# BleShield.net
KiCad netlist of a schematic drawn in EAGLE
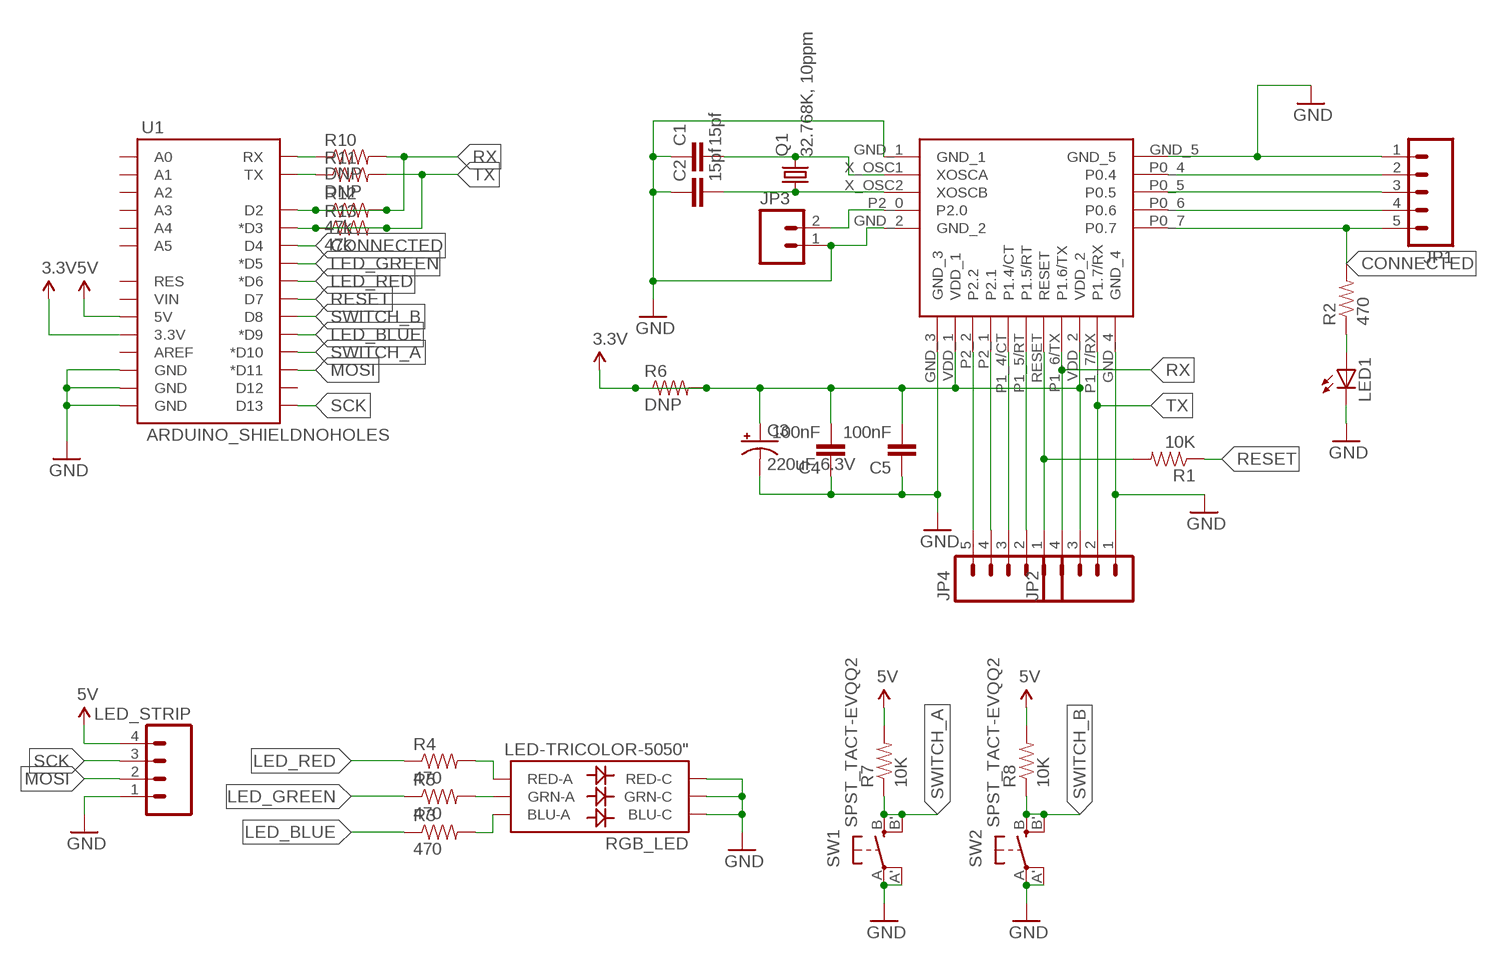
[diagram p0: schematic, sheet 1]

(export (version "E")
  (design (tool "Eeschema 10.0.6"))
  (components
    (comp (ref "C1")
      (value "15pf")
      (footprint "eagle-import:0805")
      (libsource (lib "eagle-import") (part "CAP0805"))
    )
    (comp (ref "C2")
      (value "15pf")
      (footprint "eagle-import:0805")
      (libsource (lib "eagle-import") (part "CAP0805"))
    )
    (comp (ref "C3")
      (value "220uF 6.3V")
      (footprint "eagle-import:C_6032-28R")
      (libsource (lib "eagle-import") (part "CPOL-USC/6032-28R"))
    )
    (comp (ref "C4")
      (value "100nF")
      (footprint "eagle-import:0805")
      (libsource (lib "eagle-import") (part "CAP0805"))
    )
    (comp (ref "C5")
      (value "100nF")
      (footprint "eagle-import:0805")
      (libsource (lib "eagle-import") (part "CAP0805"))
    )
    (comp (ref "JP1")
      (value "M051.27MM")
      (footprint "eagle-import:1X05-1.27MM")
      (libsource (lib "eagle-import") (part "M051.27MM"))
    )
    (comp (ref "JP2")
      (value "M041.27MM")
      (footprint "eagle-import:1X04-1.27MM")
      (libsource (lib "eagle-import") (part "M041.27MM"))
    )
    (comp (ref "JP3")
      (value "M02")
      (footprint "eagle-import:1X02-1.27MM")
      (libsource (lib "eagle-import") (part "M02"))
    )
    (comp (ref "JP4")
      (value "M051.27MM")
      (footprint "eagle-import:1X05-1.27MM")
      (libsource (lib "eagle-import") (part "M051.27MM"))
    )
    (comp (ref "LED1")
      (value "LEDCHIPLED_0805")
      (footprint "eagle-import:CHIPLED_0805")
      (libsource (lib "eagle-import") (part "LEDCHIPLED_0805"))
    )
    (comp (ref "LED_STRIP")
      (value "M04PTH")
      (footprint "eagle-import:1X04")
      (libsource (lib "eagle-import") (part "M04PTH"))
    )
    (comp (ref "Q1")
      (value "32.768K, 10ppm")
      (footprint "eagle-import:CRYSTAL_3215")
      (libsource (lib "eagle-import") (part "CRYSTAL3215"))
    )
    (comp (ref "R1")
      (value "10K")
      (footprint "eagle-import:0805")
      (libsource (lib "eagle-import") (part "RESISTOR0805-RES"))
    )
    (comp (ref "R2")
      (value "470")
      (footprint "eagle-import:0805")
      (libsource (lib "eagle-import") (part "RESISTOR0805-RES"))
    )
    (comp (ref "R3")
      (value "470")
      (footprint "eagle-import:0805")
      (libsource (lib "eagle-import") (part "RESISTOR0805-RES"))
    )
    (comp (ref "R4")
      (value "470")
      (footprint "eagle-import:0805")
      (libsource (lib "eagle-import") (part "RESISTOR0805-RES"))
    )
    (comp (ref "R5")
      (value "470")
      (footprint "eagle-import:0805")
      (libsource (lib "eagle-import") (part "RESISTOR0805-RES"))
    )
    (comp (ref "R6")
      (value "DNP")
      (footprint "eagle-import:0805")
      (libsource (lib "eagle-import") (part "RESISTOR0805-RES"))
    )
    (comp (ref "R7")
      (value "10K")
      (footprint "eagle-import:0805")
      (libsource (lib "eagle-import") (part "RESISTOR0805-RES"))
    )
    (comp (ref "R8")
      (value "10K")
      (footprint "eagle-import:0805")
      (libsource (lib "eagle-import") (part "RESISTOR0805-RES"))
    )
    (comp (ref "R10")
      (value "DNP")
      (footprint "eagle-import:0805")
      (libsource (lib "eagle-import") (part "RESISTOR0805-RES"))
    )
    (comp (ref "R11")
      (value "DNP")
      (footprint "eagle-import:0805")
      (libsource (lib "eagle-import") (part "RESISTOR0805-RES"))
    )
    (comp (ref "R12")
      (value "47k")
      (footprint "eagle-import:0805")
      (libsource (lib "eagle-import") (part "RESISTOR0805-RES"))
    )
    (comp (ref "R13")
      (value "47k")
      (footprint "eagle-import:0805")
      (libsource (lib "eagle-import") (part "RESISTOR0805-RES"))
    )
    (comp (ref "RGB_LED")
      (value "LED-TRICOLOR-5050\"")
      (footprint "eagle-import:LED-TRICOLOR-5050-FIXED")
      (libsource (lib "eagle-import") (part "LED-TRICOLOR-5050{dblquote}"))
    )
    (comp (ref "SW1")
      (value "SPST_TACT-EVQQ2")
      (footprint "eagle-import:EVQ-Q2")
      (libsource (lib "eagle-import") (part "SPST_TACT-EVQQ2"))
    )
    (comp (ref "SW2")
      (value "SPST_TACT-EVQQ2")
      (footprint "eagle-import:EVQ-Q2")
      (libsource (lib "eagle-import") (part "SPST_TACT-EVQQ2"))
    )
    (comp (ref "U$1")
      (value "BG213L")
      (footprint "eagle-import:BG312L")
      (libsource (lib "eagle-import") (part "BG213L"))
    )
    (comp (ref "U1")
      (value "ARDUINO_SHIELDNOHOLES")
      (footprint "eagle-import:DUEMILANOVE_SHIELD_NOHOLES")
      (libsource (lib "eagle-import") (part "ARDUINO_SHIELDNOHOLES"))
    )
  )
  (nets
    (net (code "1") (name "3.3V") (class "Default")
      (node (ref "C3") (pin "+") (pinfunction "+_+") (pintype "passive"))
      (node (ref "C4") (pin "2") (pinfunction "2_2") (pintype "passive"))
      (node (ref "C5") (pin "2") (pinfunction "2_2") (pintype "passive"))
      (node (ref "JP2") (pin "3") (pinfunction "3_3") (pintype "passive"))
      (node (ref "R6") (pin "1") (pinfunction "1_1") (pintype "passive"))
      (node (ref "R6") (pin "2") (pinfunction "2_2") (pintype "passive"))
      (node (ref "U$1") (pin "VDD_1") (pinfunction "VDD_1_VDD_1") (pintype "bidirectional"))
      (node (ref "U$1") (pin "VDD_2") (pinfunction "VDD_2_VDD_2") (pintype "bidirectional"))
      (node (ref "U1") (pin "3.3V") (pinfunction "3.3V_3.3V") (pintype "bidirectional"))
    )
    (net (code "2") (name "5V") (class "Default")
      (node (ref "LED_STRIP") (pin "4") (pinfunction "4_4") (pintype "passive"))
      (node (ref "R7") (pin "2") (pinfunction "2_2") (pintype "passive"))
      (node (ref "R8") (pin "2") (pinfunction "2_2") (pintype "passive"))
      (node (ref "U1") (pin "5V") (pinfunction "5V_5V") (pintype "bidirectional"))
    )
    (net (code "3") (name "CONNECTED") (class "Default")
      (node (ref "JP1") (pin "5") (pinfunction "5_5") (pintype "passive"))
      (node (ref "R2") (pin "2") (pinfunction "2_2") (pintype "passive"))
      (node (ref "U$1") (pin "P0_7") (pinfunction "P0.7_P0_7") (pintype "bidirectional"))
      (node (ref "U1") (pin "D4") (pinfunction "D4_D4") (pintype "bidirectional"))
    )
    (net (code "4") (name "GND") (class "Default")
      (node (ref "C1") (pin "1") (pinfunction "1_1") (pintype "passive"))
      (node (ref "C2") (pin "1") (pinfunction "1_1") (pintype "passive"))
      (node (ref "C3") (pin "-") (pinfunction "-_-") (pintype "passive"))
      (node (ref "C4") (pin "1") (pinfunction "1_1") (pintype "passive"))
      (node (ref "C5") (pin "1") (pinfunction "1_1") (pintype "passive"))
      (node (ref "JP1") (pin "1") (pinfunction "1_1") (pintype "passive"))
      (node (ref "JP2") (pin "1") (pinfunction "1_1") (pintype "passive"))
      (node (ref "JP3") (pin "1") (pinfunction "1_1") (pintype "passive"))
      (node (ref "LED1") (pin "C") (pinfunction "C_C") (pintype "passive"))
      (node (ref "LED_STRIP") (pin "1") (pinfunction "1_1") (pintype "passive"))
      (node (ref "RGB_LED") (pin "1") (pinfunction "BLU-C_1") (pintype "bidirectional"))
      (node (ref "RGB_LED") (pin "2") (pinfunction "RED-C_2") (pintype "bidirectional"))
      (node (ref "RGB_LED") (pin "3") (pinfunction "GRN-C_3") (pintype "bidirectional"))
      (node (ref "SW1") (pin "A") (pinfunction "P_A") (pintype "passive"))
      (node (ref "SW1") (pin "A'") (pinfunction "P1_A'") (pintype "passive"))
      (node (ref "SW2") (pin "A") (pinfunction "P_A") (pintype "passive"))
      (node (ref "SW2") (pin "A'") (pinfunction "P1_A'") (pintype "passive"))
      (node (ref "U$1") (pin "GND_1") (pinfunction "GND_1_GND_1") (pintype "bidirectional"))
      (node (ref "U$1") (pin "GND_2") (pinfunction "GND_2_GND_2") (pintype "bidirectional"))
      (node (ref "U$1") (pin "GND_3") (pinfunction "GND_3_GND_3") (pintype "bidirectional"))
      (node (ref "U$1") (pin "GND_4") (pinfunction "GND_4_GND_4") (pintype "bidirectional"))
      (node (ref "U$1") (pin "GND_5") (pinfunction "GND_5_GND_5") (pintype "bidirectional"))
      (node (ref "U1") (pin "GND@0") (pinfunction "GND_GND@0") (pintype "bidirectional"))
      (node (ref "U1") (pin "GND@1") (pinfunction "GND_GND@1") (pintype "bidirectional"))
      (node (ref "U1") (pin "GND@2") (pinfunction "GND_GND@2") (pintype "bidirectional"))
    )
    (net (code "5") (name "LED_BLUE") (class "Default")
      (node (ref "R3") (pin "1") (pinfunction "1_1") (pintype "passive"))
      (node (ref "U1") (pin "D9") (pinfunction "*D9_D9") (pintype "bidirectional"))
    )
    (net (code "6") (name "LED_GREEN") (class "Default")
      (node (ref "R5") (pin "1") (pinfunction "1_1") (pintype "passive"))
      (node (ref "U1") (pin "D5") (pinfunction "*D5_D5") (pintype "bidirectional"))
    )
    (net (code "7") (name "LED_RED") (class "Default")
      (node (ref "R4") (pin "1") (pinfunction "1_1") (pintype "passive"))
      (node (ref "U1") (pin "D6") (pinfunction "*D6_D6") (pintype "bidirectional"))
    )
    (net (code "8") (name "MOSI") (class "Default")
      (node (ref "LED_STRIP") (pin "2") (pinfunction "2_2") (pintype "passive"))
      (node (ref "U1") (pin "D11") (pinfunction "*D11_D11") (pintype "bidirectional"))
    )
    (net (code "9") (name "Net-(JP4-Pad1)") (class "Default")
      (node (ref "JP4") (pin "1") (pinfunction "1_1") (pintype "passive"))
      (node (ref "R1") (pin "2") (pinfunction "2_2") (pintype "passive"))
      (node (ref "U$1") (pin "RESET") (pinfunction "RESET_RESET") (pintype "bidirectional"))
    )
    (net (code "10") (name "Net-(LED1-PadA)") (class "Default")
      (node (ref "LED1") (pin "A") (pinfunction "A_A") (pintype "passive"))
      (node (ref "R2") (pin "1") (pinfunction "1_1") (pintype "passive"))
    )
    (net (code "11") (name "Net-(Q1-1)") (class "Default")
      (node (ref "C2") (pin "2") (pinfunction "2_2") (pintype "passive"))
      (node (ref "Q1") (pin "P$1") (pinfunction "1_P$1") (pintype "passive"))
      (node (ref "U$1") (pin "X_OSC2") (pinfunction "XOSCB_X_OSC2") (pintype "bidirectional"))
    )
    (net (code "12") (name "Net-(Q1-2)") (class "Default")
      (node (ref "C1") (pin "2") (pinfunction "2_2") (pintype "passive"))
      (node (ref "Q1") (pin "P$2") (pinfunction "2_P$2") (pintype "passive"))
      (node (ref "U$1") (pin "X_OSC1") (pinfunction "XOSCA_X_OSC1") (pintype "bidirectional"))
    )
    (net (code "13") (name "Net-(R10-Pad1)") (class "Default")
      (node (ref "R10") (pin "1") (pinfunction "1_1") (pintype "passive"))
      (node (ref "U1") (pin "RX") (pinfunction "RX_RX") (pintype "bidirectional"))
    )
    (net (code "14") (name "Net-(R11-Pad1)") (class "Default")
      (node (ref "R11") (pin "1") (pinfunction "1_1") (pintype "passive"))
      (node (ref "U1") (pin "TX") (pinfunction "TX_TX") (pintype "bidirectional"))
    )
    (net (code "15") (name "Net-(RGB_LED-BLU-A)") (class "Default")
      (node (ref "R3") (pin "2") (pinfunction "2_2") (pintype "passive"))
      (node (ref "RGB_LED") (pin "6") (pinfunction "BLU-A_6") (pintype "bidirectional"))
    )
    (net (code "16") (name "Net-(RGB_LED-GRN-A)") (class "Default")
      (node (ref "R5") (pin "2") (pinfunction "2_2") (pintype "passive"))
      (node (ref "RGB_LED") (pin "4") (pinfunction "GRN-A_4") (pintype "bidirectional"))
    )
    (net (code "17") (name "Net-(RGB_LED-RED-A)") (class "Default")
      (node (ref "R4") (pin "2") (pinfunction "2_2") (pintype "passive"))
      (node (ref "RGB_LED") (pin "5") (pinfunction "RED-A_5") (pintype "bidirectional"))
    )
    (net (code "18") (name "Net-(U$1-P0.4)") (class "Default")
      (node (ref "JP1") (pin "2") (pinfunction "2_2") (pintype "passive"))
      (node (ref "U$1") (pin "P0_4") (pinfunction "P0.4_P0_4") (pintype "bidirectional"))
    )
    (net (code "19") (name "Net-(U$1-P0.5)") (class "Default")
      (node (ref "JP1") (pin "3") (pinfunction "3_3") (pintype "passive"))
      (node (ref "U$1") (pin "P0_5") (pinfunction "P0.5_P0_5") (pintype "bidirectional"))
    )
    (net (code "20") (name "Net-(U$1-P0.6)") (class "Default")
      (node (ref "JP1") (pin "4") (pinfunction "4_4") (pintype "passive"))
      (node (ref "U$1") (pin "P0_6") (pinfunction "P0.6_P0_6") (pintype "bidirectional"))
    )
    (net (code "21") (name "Net-(U$1-P1.4{slash}CT)") (class "Default")
      (node (ref "JP4") (pin "3") (pinfunction "3_3") (pintype "passive"))
      (node (ref "U$1") (pin "P1_4/CT") (pinfunction "P1.4/CT_P1_4/CT") (pintype "bidirectional"))
    )
    (net (code "22") (name "Net-(U$1-P1.5{slash}RT)") (class "Default")
      (node (ref "JP4") (pin "2") (pinfunction "2_2") (pintype "passive"))
      (node (ref "U$1") (pin "P1_5/RT") (pinfunction "P1.5/RT_P1_5/RT") (pintype "bidirectional"))
    )
    (net (code "23") (name "Net-(U$1-P2.0)") (class "Default")
      (node (ref "JP3") (pin "2") (pinfunction "2_2") (pintype "passive"))
      (node (ref "U$1") (pin "P2_0") (pinfunction "P2.0_P2_0") (pintype "bidirectional"))
    )
    (net (code "24") (name "Net-(U$1-P2.1)") (class "Default")
      (node (ref "JP4") (pin "4") (pinfunction "4_4") (pintype "passive"))
      (node (ref "U$1") (pin "P2_1") (pinfunction "P2.1_P2_1") (pintype "bidirectional"))
    )
    (net (code "25") (name "Net-(U$1-P2.2)") (class "Default")
      (node (ref "JP4") (pin "5") (pinfunction "5_5") (pintype "passive"))
      (node (ref "U$1") (pin "P2_2") (pinfunction "P2.2_P2_2") (pintype "bidirectional"))
    )
    (net (code "26") (name "RESET") (class "Default")
      (node (ref "R1") (pin "1") (pinfunction "1_1") (pintype "passive"))
      (node (ref "U1") (pin "D7") (pinfunction "D7_D7") (pintype "bidirectional"))
    )
    (net (code "27") (name "RX") (class "Default")
      (node (ref "JP2") (pin "4") (pinfunction "4_4") (pintype "passive"))
      (node (ref "R10") (pin "2") (pinfunction "2_2") (pintype "passive"))
      (node (ref "R12") (pin "1") (pinfunction "1_1") (pintype "passive"))
      (node (ref "R12") (pin "2") (pinfunction "2_2") (pintype "passive"))
      (node (ref "U$1") (pin "P1_6/TX") (pinfunction "P1.6/TX_P1_6/TX") (pintype "bidirectional"))
      (node (ref "U1") (pin "D2") (pinfunction "D2_D2") (pintype "bidirectional"))
    )
    (net (code "28") (name "SCK") (class "Default")
      (node (ref "LED_STRIP") (pin "3") (pinfunction "3_3") (pintype "passive"))
      (node (ref "U1") (pin "D13") (pinfunction "D13_D13") (pintype "bidirectional"))
    )
    (net (code "29") (name "SWITCH_A") (class "Default")
      (node (ref "R7") (pin "1") (pinfunction "1_1") (pintype "passive"))
      (node (ref "SW1") (pin "B") (pinfunction "S_B") (pintype "passive"))
      (node (ref "SW1") (pin "B'") (pinfunction "S1_B'") (pintype "passive"))
      (node (ref "U1") (pin "D10") (pinfunction "*D10_D10") (pintype "bidirectional"))
    )
    (net (code "30") (name "SWITCH_B") (class "Default")
      (node (ref "R8") (pin "1") (pinfunction "1_1") (pintype "passive"))
      (node (ref "SW2") (pin "B") (pinfunction "S_B") (pintype "passive"))
      (node (ref "SW2") (pin "B'") (pinfunction "S1_B'") (pintype "passive"))
      (node (ref "U1") (pin "D8") (pinfunction "D8_D8") (pintype "bidirectional"))
    )
    (net (code "31") (name "TX") (class "Default")
      (node (ref "JP2") (pin "2") (pinfunction "2_2") (pintype "passive"))
      (node (ref "R11") (pin "2") (pinfunction "2_2") (pintype "passive"))
      (node (ref "R13") (pin "1") (pinfunction "1_1") (pintype "passive"))
      (node (ref "R13") (pin "2") (pinfunction "2_2") (pintype "passive"))
      (node (ref "U$1") (pin "P1_7/RX") (pinfunction "P1.7/RX_P1_7/RX") (pintype "bidirectional"))
      (node (ref "U1") (pin "D3") (pinfunction "*D3_D3") (pintype "bidirectional"))
    )
    (net (code "32") (name "unconnected-(U1-PadA0)") (class "Default")
      (node (ref "U1") (pin "A0") (pinfunction "A0_A0") (pintype "bidirectional"))
    )
    (net (code "33") (name "unconnected-(U1-PadA1)") (class "Default")
      (node (ref "U1") (pin "A1") (pinfunction "A1_A1") (pintype "bidirectional"))
    )
    (net (code "34") (name "unconnected-(U1-PadA2)") (class "Default")
      (node (ref "U1") (pin "A2") (pinfunction "A2_A2") (pintype "bidirectional"))
    )
    (net (code "35") (name "unconnected-(U1-PadA3)") (class "Default")
      (node (ref "U1") (pin "A3") (pinfunction "A3_A3") (pintype "bidirectional"))
    )
    (net (code "36") (name "unconnected-(U1-PadA4)") (class "Default")
      (node (ref "U1") (pin "A4") (pinfunction "A4_A4") (pintype "bidirectional"))
    )
    (net (code "37") (name "unconnected-(U1-PadA5)") (class "Default")
      (node (ref "U1") (pin "A5") (pinfunction "A5_A5") (pintype "bidirectional"))
    )
    (net (code "38") (name "unconnected-(U1-PadAREF)") (class "Default")
      (node (ref "U1") (pin "AREF") (pinfunction "AREF_AREF") (pintype "bidirectional"))
    )
    (net (code "39") (name "unconnected-(U1-PadD12)") (class "Default")
      (node (ref "U1") (pin "D12") (pinfunction "D12_D12") (pintype "bidirectional"))
    )
    (net (code "40") (name "unconnected-(U1-PadRES)") (class "Default")
      (node (ref "U1") (pin "RES") (pinfunction "RES_RES") (pintype "bidirectional"))
    )
    (net (code "41") (name "unconnected-(U1-PadVIN)") (class "Default")
      (node (ref "U1") (pin "VIN") (pinfunction "VIN_VIN") (pintype "bidirectional"))
    )
  )
)
